# 2020can_master_v5.net
KiCad netlist of a schematic drawn in EAGLE
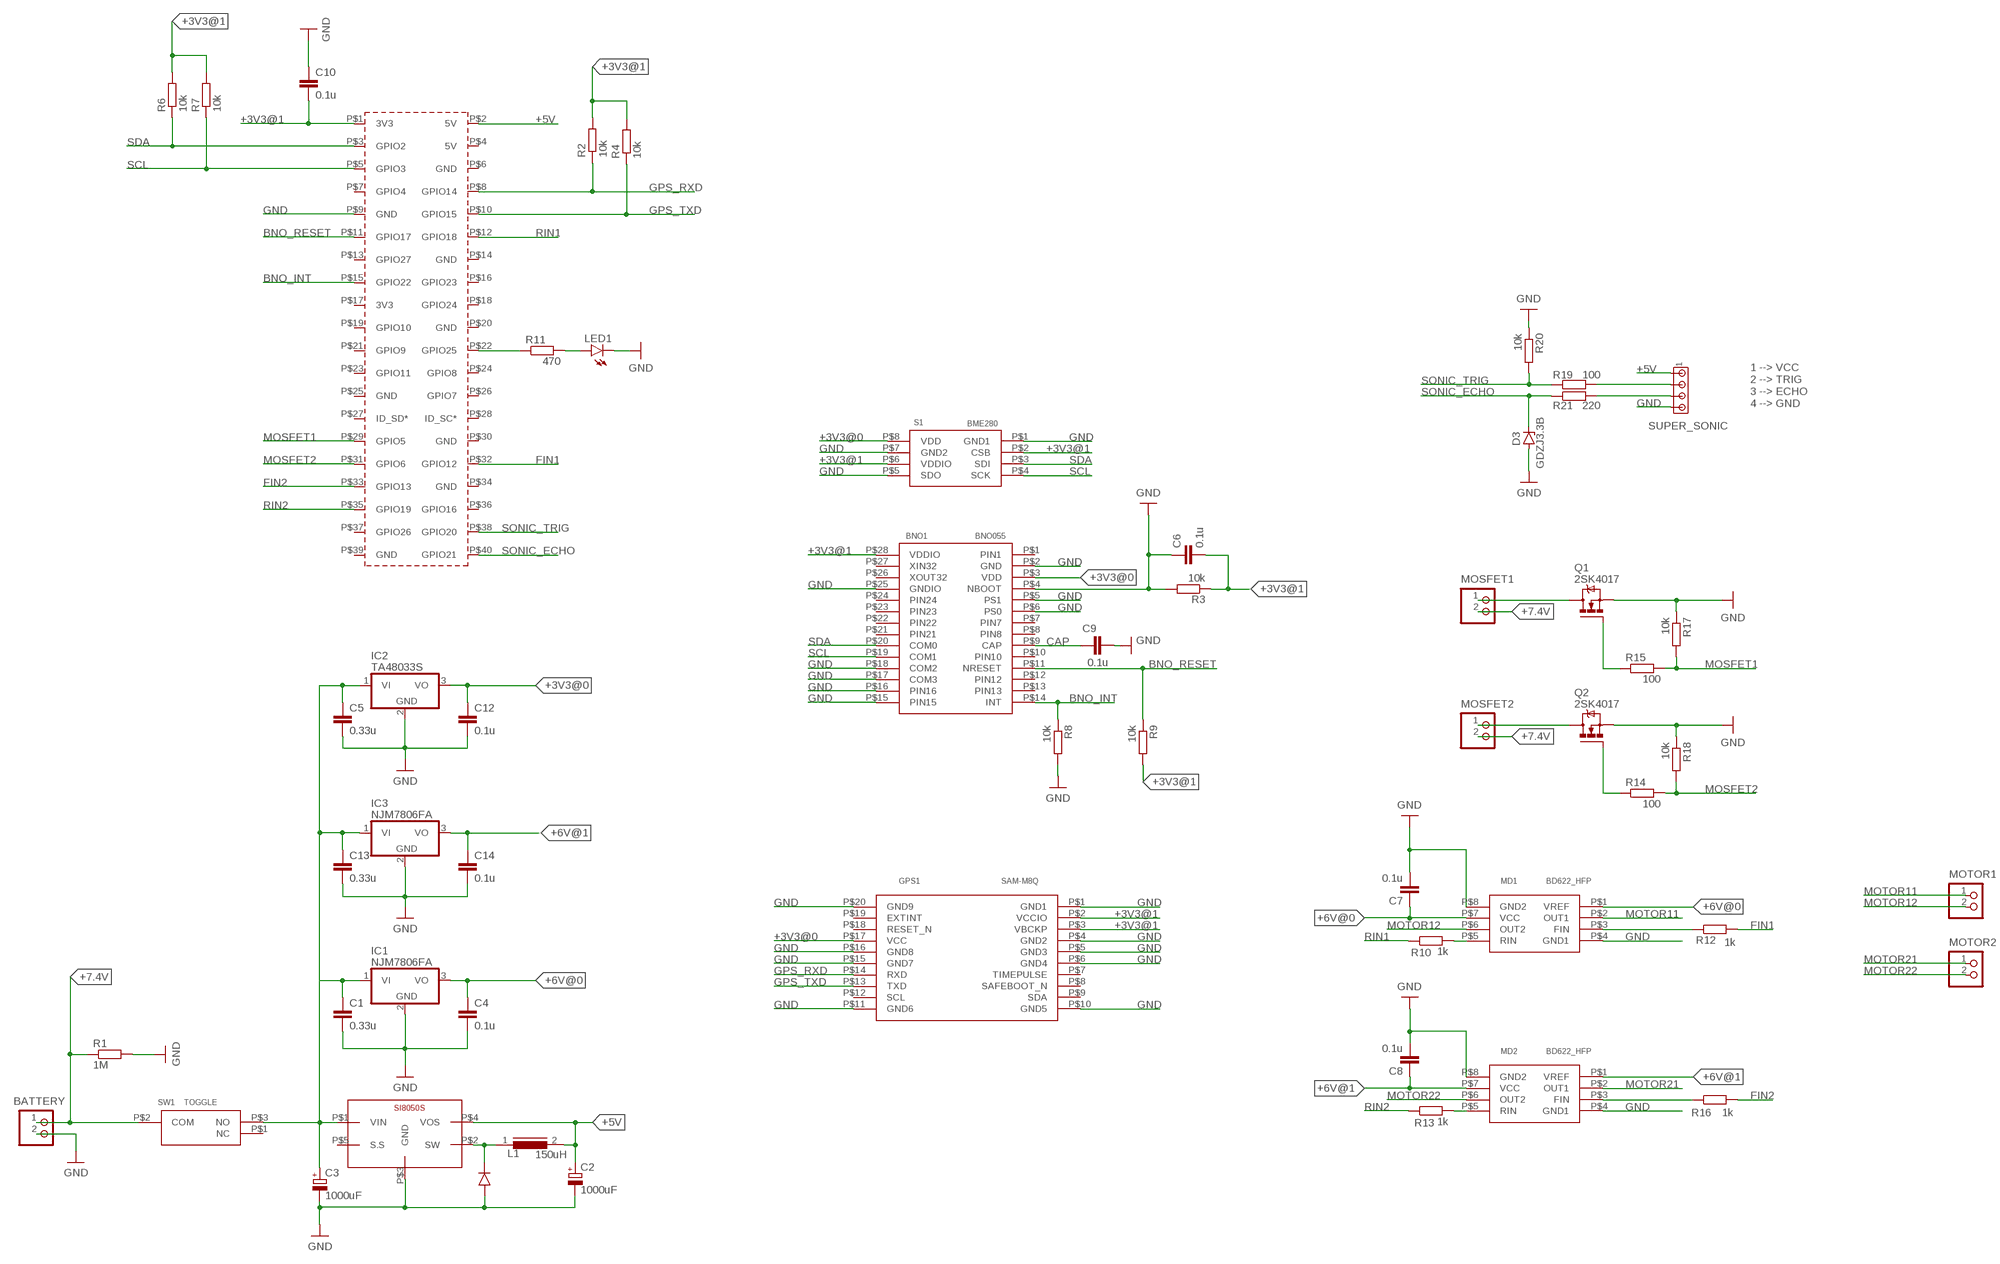
[diagram p0: schematic, sheet 1]

(export (version "E")
  (design (tool "Eeschema 10.0.6"))
  (components
    (comp (ref "BATTERY")
      (value "B2P-VH")
      (footprint "eagle-import:B2P-VH")
      (libsource (lib "eagle-import") (part "B2P-VH"))
    )
    (comp (ref "BNO1")
      (value "BNO055")
      (footprint "eagle-import:BNO055")
      (libsource (lib "eagle-import") (part "BNO055"))
    )
    (comp (ref "C1")
      (value "0.33u")
      (footprint "eagle-import:C5B3")
      (libsource (lib "eagle-import") (part "C5/3"))
    )
    (comp (ref "C2")
      (value "1000uF")
      (footprint "eagle-import:E5-10,5")
      (libsource (lib "eagle-import") (part "CPOL-EUE5-10.5"))
    )
    (comp (ref "C3")
      (value "1000uF")
      (footprint "eagle-import:E5-10,5")
      (libsource (lib "eagle-import") (part "CPOL-EUE5-10.5"))
    )
    (comp (ref "C4")
      (value "0.1u")
      (footprint "eagle-import:C5B3")
      (libsource (lib "eagle-import") (part "C5/3"))
    )
    (comp (ref "C5")
      (value "0.33u")
      (footprint "eagle-import:C5B3")
      (libsource (lib "eagle-import") (part "C5/3"))
    )
    (comp (ref "C6")
      (value "0.1u")
      (footprint "eagle-import:C1206")
      (libsource (lib "eagle-import") (part "C-EUC1206"))
    )
    (comp (ref "C7")
      (value "0.1u")
      (footprint "eagle-import:C1206")
      (libsource (lib "eagle-import") (part "C-EUC1206"))
    )
    (comp (ref "C8")
      (value "0.1u")
      (footprint "eagle-import:C1206")
      (libsource (lib "eagle-import") (part "C-EUC1206"))
    )
    (comp (ref "C9")
      (value "0.1u")
      (footprint "eagle-import:C1206")
      (libsource (lib "eagle-import") (part "C-EUC1206"))
    )
    (comp (ref "C10")
      (value "0.1u")
      (footprint "eagle-import:C1206")
      (libsource (lib "eagle-import") (part "C-EUC1206"))
    )
    (comp (ref "C12")
      (value "0.1u")
      (footprint "eagle-import:C5B3")
      (libsource (lib "eagle-import") (part "C5/3"))
    )
    (comp (ref "C13")
      (value "0.33u")
      (footprint "eagle-import:C5B3")
      (libsource (lib "eagle-import") (part "C5/3"))
    )
    (comp (ref "C14")
      (value "0.1u")
      (footprint "eagle-import:C5B3")
      (libsource (lib "eagle-import") (part "C5/3"))
    )
    (comp (ref "D3")
      (value "GDZJ3.3B")
      (footprint "eagle-import:DO35Z10")
      (libsource (lib "eagle-import") (part "1N821"))
    )
    (comp (ref "DIODE_1.1")
      (value "DIODE_1.5")
      (footprint "eagle-import:DIODE_1.5")
      (libsource (lib "eagle-import") (part "DIODE_1.5"))
    )
    (comp (ref "GPS1")
      (value "SAM-M8Q")
      (footprint "eagle-import:SAM-M8Q")
      (libsource (lib "eagle-import") (part "SAM-M8Q"))
    )
    (comp (ref "IC1")
      (value "NJM7806FA")
      (footprint "eagle-import:TO220V")
      (libsource (lib "eagle-import") (part "78TV6"))
    )
    (comp (ref "IC2")
      (value "TA48033S")
      (footprint "eagle-import:TO220V")
      (libsource (lib "eagle-import") (part "78TV6"))
    )
    (comp (ref "IC3")
      (value "NJM7806FA")
      (footprint "eagle-import:TO220V")
      (libsource (lib "eagle-import") (part "78TV6"))
    )
    (comp (ref "L1")
      (value "150uH")
      (footprint "eagle-import:SFT830D")
      (libsource (lib "eagle-import") (part "SFT830D"))
    )
    (comp (ref "LED1")
      (value "LED5MM")
      (footprint "eagle-import:LED5MM")
      (libsource (lib "eagle-import") (part "LED5MM"))
    )
    (comp (ref "MD1")
      (value "BD622_HFP")
      (footprint "eagle-import:BD62___HRP7")
      (libsource (lib "eagle-import") (part "BD622_HFP"))
    )
    (comp (ref "MD2")
      (value "BD622_HFP")
      (footprint "eagle-import:BD62___HRP7")
      (libsource (lib "eagle-import") (part "BD622_HFP"))
    )
    (comp (ref "MOSFET1")
      (value "B2P-VH")
      (footprint "eagle-import:B2P-VH")
      (libsource (lib "eagle-import") (part "B2P-VH"))
    )
    (comp (ref "MOSFET2")
      (value "B2P-VH")
      (footprint "eagle-import:B2P-VH")
      (libsource (lib "eagle-import") (part "B2P-VH"))
    )
    (comp (ref "MOTOR1")
      (value "B2P-VH")
      (footprint "eagle-import:B2P-VH")
      (libsource (lib "eagle-import") (part "B2P-VH"))
    )
    (comp (ref "MOTOR2")
      (value "B2P-VH")
      (footprint "eagle-import:B2P-VH")
      (libsource (lib "eagle-import") (part "B2P-VH"))
    )
    (comp (ref "PCB1")
      (value "RPI3RPI3")
      (footprint "eagle-import:RPI3")
      (libsource (lib "eagle-import") (part "RPI3RPI3"))
    )
    (comp (ref "Q1")
      (value "2SK4017")
      (footprint "eagle-import:TO220BV")
      (libsource (lib "eagle-import") (part "IRF520"))
    )
    (comp (ref "Q2")
      (value "2SK4017")
      (footprint "eagle-import:TO220BV")
      (libsource (lib "eagle-import") (part "IRF520"))
    )
    (comp (ref "R1")
      (value "1M")
      (footprint "eagle-import:R2012")
      (libsource (lib "eagle-import") (part "R-EU_R2012"))
    )
    (comp (ref "R2")
      (value "10k")
      (footprint "eagle-import:R2012")
      (libsource (lib "eagle-import") (part "R-EU_R2012"))
    )
    (comp (ref "R3")
      (value "10k")
      (footprint "eagle-import:R2012")
      (libsource (lib "eagle-import") (part "R-EU_R2012"))
    )
    (comp (ref "R4")
      (value "10k")
      (footprint "eagle-import:R2012")
      (libsource (lib "eagle-import") (part "R-EU_R2012"))
    )
    (comp (ref "R6")
      (value "10k")
      (footprint "eagle-import:R2012")
      (libsource (lib "eagle-import") (part "R-EU_R2012"))
    )
    (comp (ref "R7")
      (value "10k")
      (footprint "eagle-import:R2012")
      (libsource (lib "eagle-import") (part "R-EU_R2012"))
    )
    (comp (ref "R8")
      (value "10k")
      (footprint "eagle-import:R2012")
      (libsource (lib "eagle-import") (part "R-EU_R2012"))
    )
    (comp (ref "R9")
      (value "10k")
      (footprint "eagle-import:R2012")
      (libsource (lib "eagle-import") (part "R-EU_R2012"))
    )
    (comp (ref "R10")
      (value "1k")
      (footprint "eagle-import:R2012")
      (libsource (lib "eagle-import") (part "R-EU_R2012"))
    )
    (comp (ref "R11")
      (value "470")
      (footprint "eagle-import:0207_10")
      (libsource (lib "eagle-import") (part "R-EU_0207/10"))
    )
    (comp (ref "R12")
      (value "1k")
      (footprint "eagle-import:R2012")
      (libsource (lib "eagle-import") (part "R-EU_R2012"))
    )
    (comp (ref "R13")
      (value "1k")
      (footprint "eagle-import:R2012")
      (libsource (lib "eagle-import") (part "R-EU_R2012"))
    )
    (comp (ref "R14")
      (value "100")
      (footprint "eagle-import:0207_10")
      (libsource (lib "eagle-import") (part "R-EU_0207/10"))
    )
    (comp (ref "R15")
      (value "100")
      (footprint "eagle-import:0207_10")
      (libsource (lib "eagle-import") (part "R-EU_0207/10"))
    )
    (comp (ref "R16")
      (value "1k")
      (footprint "eagle-import:R2012")
      (libsource (lib "eagle-import") (part "R-EU_R2012"))
    )
    (comp (ref "R17")
      (value "10k")
      (footprint "eagle-import:R2012")
      (libsource (lib "eagle-import") (part "R-EU_R2012"))
    )
    (comp (ref "R18")
      (value "10k")
      (footprint "eagle-import:R2012")
      (libsource (lib "eagle-import") (part "R-EU_R2012"))
    )
    (comp (ref "R19")
      (value "100")
      (footprint "eagle-import:0207_10")
      (libsource (lib "eagle-import") (part "R-EU_0207/10"))
    )
    (comp (ref "R20")
      (value "10k")
      (footprint "eagle-import:R2012")
      (libsource (lib "eagle-import") (part "R-EU_R2012"))
    )
    (comp (ref "R21")
      (value "220")
      (footprint "eagle-import:0207_10")
      (libsource (lib "eagle-import") (part "R-EU_0207/10"))
    )
    (comp (ref "S1")
      (value "BME280")
      (footprint "eagle-import:BME280")
      (libsource (lib "eagle-import") (part "BME280"))
    )
    (comp (ref "SI8050S1")
      (value "SI8050S")
      (footprint "eagle-import:SI8050S")
      (libsource (lib "eagle-import") (part "SI8050S"))
    )
    (comp (ref "SUPER_SONIC")
      (value "MTA04-100")
      (footprint "eagle-import:10X04MTA")
      (libsource (lib "eagle-import") (part "MTA04-100"))
    )
    (comp (ref "SW1")
      (value "TOGGLE")
      (footprint "eagle-import:TOGGLE_1MS1-T1-B1-M2-Q-N-S")
      (libsource (lib "eagle-import") (part "TOGGLE_1MS1-T1-B1-M2-Q-N-S"))
    )
  )
  (nets
    (net (code "1") (name "+3V3@0") (class "Default")
      (node (ref "BNO1") (pin "P$3") (pinfunction "VDD_P$3") (pintype "bidirectional"))
      (node (ref "C12") (pin "1") (pinfunction "1_1") (pintype "passive"))
      (node (ref "GPS1") (pin "P$17") (pinfunction "VCC_P$17") (pintype "bidirectional"))
      (node (ref "IC2") (pin "3") (pinfunction "VO_3") (pintype "passive"))
      (node (ref "S1") (pin "P$8") (pinfunction "VDD_P$8") (pintype "bidirectional"))
    )
    (net (code "2") (name "+3V3@1") (class "Default")
      (node (ref "BNO1") (pin "P$28") (pinfunction "VDDIO_P$28") (pintype "bidirectional"))
      (node (ref "C10") (pin "2") (pinfunction "2_2") (pintype "passive"))
      (node (ref "C6") (pin "2") (pinfunction "2_2") (pintype "passive"))
      (node (ref "GPS1") (pin "P$2") (pinfunction "VCCIO_P$2") (pintype "bidirectional"))
      (node (ref "GPS1") (pin "P$3") (pinfunction "VBCKP_P$3") (pintype "bidirectional"))
      (node (ref "PCB1") (pin "P$1") (pinfunction "3V3_P$1") (pintype "bidirectional"))
      (node (ref "R2") (pin "2") (pinfunction "2_2") (pintype "passive"))
      (node (ref "R3") (pin "1") (pinfunction "1_1") (pintype "passive"))
      (node (ref "R4") (pin "2") (pinfunction "2_2") (pintype "passive"))
      (node (ref "R6") (pin "2") (pinfunction "2_2") (pintype "passive"))
      (node (ref "R7") (pin "2") (pinfunction "2_2") (pintype "passive"))
      (node (ref "R9") (pin "2") (pinfunction "2_2") (pintype "passive"))
      (node (ref "S1") (pin "P$2") (pinfunction "CSB_P$2") (pintype "bidirectional"))
      (node (ref "S1") (pin "P$6") (pinfunction "VDDIO_P$6") (pintype "bidirectional"))
    )
    (net (code "3") (name "+5V") (class "Default")
      (node (ref "C2") (pin "+") (pinfunction "+_+") (pintype "passive"))
      (node (ref "L1") (pin "2") (pinfunction "2_2") (pintype "passive"))
      (node (ref "PCB1") (pin "P$2") (pinfunction "5V_P$2") (pintype "bidirectional"))
      (node (ref "SI8050S1") (pin "P$4") (pinfunction "VOS_P$4") (pintype "bidirectional"))
      (node (ref "SUPER_SONIC") (pin "1") (pinfunction "1_1") (pintype "passive"))
    )
    (net (code "4") (name "+6V@0") (class "Default")
      (node (ref "C4") (pin "1") (pinfunction "1_1") (pintype "passive"))
      (node (ref "C7") (pin "1") (pinfunction "1_1") (pintype "passive"))
      (node (ref "IC1") (pin "3") (pinfunction "VO_3") (pintype "passive"))
      (node (ref "MD1") (pin "P$1") (pinfunction "VREF_P$1") (pintype "bidirectional"))
      (node (ref "MD1") (pin "P$7") (pinfunction "VCC_P$7") (pintype "bidirectional"))
    )
    (net (code "5") (name "+6V@1") (class "Default")
      (node (ref "C14") (pin "1") (pinfunction "1_1") (pintype "passive"))
      (node (ref "C8") (pin "1") (pinfunction "1_1") (pintype "passive"))
      (node (ref "IC3") (pin "3") (pinfunction "VO_3") (pintype "passive"))
      (node (ref "MD2") (pin "P$1") (pinfunction "VREF_P$1") (pintype "bidirectional"))
      (node (ref "MD2") (pin "P$7") (pinfunction "VCC_P$7") (pintype "bidirectional"))
    )
    (net (code "6") (name "+7.4V") (class "Default")
      (node (ref "BATTERY") (pin "1") (pinfunction "1_1") (pintype "passive"))
      (node (ref "MOSFET1") (pin "2") (pinfunction "2_2") (pintype "passive"))
      (node (ref "MOSFET2") (pin "2") (pinfunction "2_2") (pintype "passive"))
      (node (ref "R1") (pin "1") (pinfunction "1_1") (pintype "passive"))
      (node (ref "SW1") (pin "P$2") (pinfunction "COM_P$2") (pintype "bidirectional"))
    )
    (net (code "7") (name "/BNO_INT") (class "Default")
      (node (ref "BNO1") (pin "P$14") (pinfunction "INT_P$14") (pintype "bidirectional"))
      (node (ref "PCB1") (pin "P$15") (pinfunction "GPIO22_P$15") (pintype "bidirectional"))
      (node (ref "R8") (pin "1") (pinfunction "1_1") (pintype "passive"))
    )
    (net (code "8") (name "/BNO_RESET") (class "Default")
      (node (ref "BNO1") (pin "P$11") (pinfunction "NRESET_P$11") (pintype "bidirectional"))
      (node (ref "PCB1") (pin "P$11") (pinfunction "GPIO17_P$11") (pintype "bidirectional"))
      (node (ref "R9") (pin "1") (pinfunction "1_1") (pintype "passive"))
    )
    (net (code "9") (name "/CAP") (class "Default")
      (node (ref "BNO1") (pin "P$9") (pinfunction "CAP_P$9") (pintype "bidirectional"))
      (node (ref "C9") (pin "1") (pinfunction "1_1") (pintype "passive"))
    )
    (net (code "10") (name "/FIN1") (class "Default")
      (node (ref "PCB1") (pin "P$32") (pinfunction "GPIO12_P$32") (pintype "bidirectional"))
      (node (ref "R12") (pin "2") (pinfunction "2_2") (pintype "passive"))
    )
    (net (code "11") (name "/FIN2") (class "Default")
      (node (ref "PCB1") (pin "P$33") (pinfunction "GPIO13_P$33") (pintype "bidirectional"))
      (node (ref "R16") (pin "2") (pinfunction "2_2") (pintype "passive"))
    )
    (net (code "12") (name "/GPS_RXD") (class "Default")
      (node (ref "GPS1") (pin "P$14") (pinfunction "RXD_P$14") (pintype "bidirectional"))
      (node (ref "PCB1") (pin "P$8") (pinfunction "GPIO14_P$8") (pintype "bidirectional"))
      (node (ref "R2") (pin "1") (pinfunction "1_1") (pintype "passive"))
    )
    (net (code "13") (name "/GPS_TXD") (class "Default")
      (node (ref "GPS1") (pin "P$13") (pinfunction "TXD_P$13") (pintype "bidirectional"))
      (node (ref "PCB1") (pin "P$10") (pinfunction "GPIO15_P$10") (pintype "bidirectional"))
      (node (ref "R4") (pin "1") (pinfunction "1_1") (pintype "passive"))
    )
    (net (code "14") (name "/MOSFET1") (class "Default")
      (node (ref "PCB1") (pin "P$29") (pinfunction "GPIO5_P$29") (pintype "bidirectional"))
      (node (ref "R15") (pin "2") (pinfunction "2_2") (pintype "passive"))
      (node (ref "R17") (pin "2") (pinfunction "2_2") (pintype "passive"))
    )
    (net (code "15") (name "/MOSFET2") (class "Default")
      (node (ref "PCB1") (pin "P$31") (pinfunction "GPIO6_P$31") (pintype "bidirectional"))
      (node (ref "R14") (pin "2") (pinfunction "2_2") (pintype "passive"))
      (node (ref "R18") (pin "2") (pinfunction "2_2") (pintype "passive"))
    )
    (net (code "16") (name "/MOTOR11") (class "Default")
      (node (ref "MD1") (pin "P$2") (pinfunction "OUT1_P$2") (pintype "bidirectional"))
      (node (ref "MOTOR1") (pin "1") (pinfunction "1_1") (pintype "passive"))
    )
    (net (code "17") (name "/MOTOR12") (class "Default")
      (node (ref "MD1") (pin "P$6") (pinfunction "OUT2_P$6") (pintype "bidirectional"))
      (node (ref "MOTOR1") (pin "2") (pinfunction "2_2") (pintype "passive"))
    )
    (net (code "18") (name "/MOTOR21") (class "Default")
      (node (ref "MD2") (pin "P$2") (pinfunction "OUT1_P$2") (pintype "bidirectional"))
      (node (ref "MOTOR2") (pin "1") (pinfunction "1_1") (pintype "passive"))
    )
    (net (code "19") (name "/MOTOR22") (class "Default")
      (node (ref "MD2") (pin "P$6") (pinfunction "OUT2_P$6") (pintype "bidirectional"))
      (node (ref "MOTOR2") (pin "2") (pinfunction "2_2") (pintype "passive"))
    )
    (net (code "20") (name "/RIN1") (class "Default")
      (node (ref "PCB1") (pin "P$12") (pinfunction "GPIO18_P$12") (pintype "bidirectional"))
      (node (ref "R10") (pin "1") (pinfunction "1_1") (pintype "passive"))
    )
    (net (code "21") (name "/RIN2") (class "Default")
      (node (ref "PCB1") (pin "P$35") (pinfunction "GPIO19_P$35") (pintype "bidirectional"))
      (node (ref "R13") (pin "1") (pinfunction "1_1") (pintype "passive"))
    )
    (net (code "22") (name "/SCL") (class "Default")
      (node (ref "BNO1") (pin "P$19") (pinfunction "COM1_P$19") (pintype "bidirectional"))
      (node (ref "PCB1") (pin "P$5") (pinfunction "GPIO3_P$5") (pintype "bidirectional"))
      (node (ref "R7") (pin "1") (pinfunction "1_1") (pintype "passive"))
      (node (ref "S1") (pin "P$4") (pinfunction "SCK_P$4") (pintype "bidirectional"))
    )
    (net (code "23") (name "/SDA") (class "Default")
      (node (ref "BNO1") (pin "P$20") (pinfunction "COM0_P$20") (pintype "bidirectional"))
      (node (ref "PCB1") (pin "P$3") (pinfunction "GPIO2_P$3") (pintype "bidirectional"))
      (node (ref "R6") (pin "1") (pinfunction "1_1") (pintype "passive"))
      (node (ref "S1") (pin "P$3") (pinfunction "SDI_P$3") (pintype "bidirectional"))
    )
    (net (code "24") (name "/SONIC_ECHO") (class "Default")
      (node (ref "D3") (pin "C") (pinfunction "C_C") (pintype "passive"))
      (node (ref "PCB1") (pin "P$40") (pinfunction "GPIO21_P$40") (pintype "bidirectional"))
      (node (ref "R21") (pin "1") (pinfunction "1_1") (pintype "passive"))
    )
    (net (code "25") (name "/SONIC_TRIG") (class "Default")
      (node (ref "PCB1") (pin "P$38") (pinfunction "GPIO20_P$38") (pintype "bidirectional"))
      (node (ref "R19") (pin "1") (pinfunction "1_1") (pintype "passive"))
      (node (ref "R20") (pin "2") (pinfunction "2_2") (pintype "passive"))
    )
    (net (code "26") (name "GND") (class "Default")
      (node (ref "BATTERY") (pin "2") (pinfunction "2_2") (pintype "passive"))
      (node (ref "BNO1") (pin "P$15") (pinfunction "PIN15_P$15") (pintype "bidirectional"))
      (node (ref "BNO1") (pin "P$16") (pinfunction "PIN16_P$16") (pintype "bidirectional"))
      (node (ref "BNO1") (pin "P$17") (pinfunction "COM3_P$17") (pintype "bidirectional"))
      (node (ref "BNO1") (pin "P$18") (pinfunction "COM2_P$18") (pintype "bidirectional"))
      (node (ref "BNO1") (pin "P$2") (pinfunction "GND_P$2") (pintype "bidirectional"))
      (node (ref "BNO1") (pin "P$25") (pinfunction "GNDIO_P$25") (pintype "bidirectional"))
      (node (ref "BNO1") (pin "P$4") (pinfunction "NBOOT_P$4") (pintype "bidirectional"))
      (node (ref "BNO1") (pin "P$5") (pinfunction "PS1_P$5") (pintype "bidirectional"))
      (node (ref "BNO1") (pin "P$6") (pinfunction "PS0_P$6") (pintype "bidirectional"))
      (node (ref "C1") (pin "2") (pinfunction "2_2") (pintype "passive"))
      (node (ref "C10") (pin "1") (pinfunction "1_1") (pintype "passive"))
      (node (ref "C12") (pin "2") (pinfunction "2_2") (pintype "passive"))
      (node (ref "C2") (pin "-") (pinfunction "-_-") (pintype "passive"))
      (node (ref "C3") (pin "-") (pinfunction "-_-") (pintype "passive"))
      (node (ref "C4") (pin "2") (pinfunction "2_2") (pintype "passive"))
      (node (ref "C5") (pin "2") (pinfunction "2_2") (pintype "passive"))
      (node (ref "C6") (pin "1") (pinfunction "1_1") (pintype "passive"))
      (node (ref "C7") (pin "2") (pinfunction "2_2") (pintype "passive"))
      (node (ref "C8") (pin "2") (pinfunction "2_2") (pintype "passive"))
      (node (ref "C9") (pin "2") (pinfunction "2_2") (pintype "passive"))
      (node (ref "D3") (pin "A") (pinfunction "A_A") (pintype "passive"))
      (node (ref "DIODE_1.1") (pin "P$1") (pinfunction "ANODE_P$1") (pintype "bidirectional"))
      (node (ref "GPS1") (pin "P$1") (pinfunction "GND1_P$1") (pintype "bidirectional"))
      (node (ref "GPS1") (pin "P$10") (pinfunction "GND5_P$10") (pintype "bidirectional"))
      (node (ref "GPS1") (pin "P$11") (pinfunction "GND6_P$11") (pintype "bidirectional"))
      (node (ref "GPS1") (pin "P$15") (pinfunction "GND7_P$15") (pintype "bidirectional"))
      (node (ref "GPS1") (pin "P$16") (pinfunction "GND8_P$16") (pintype "bidirectional"))
      (node (ref "GPS1") (pin "P$20") (pinfunction "GND9_P$20") (pintype "bidirectional"))
      (node (ref "GPS1") (pin "P$4") (pinfunction "GND2_P$4") (pintype "bidirectional"))
      (node (ref "GPS1") (pin "P$5") (pinfunction "GND3_P$5") (pintype "bidirectional"))
      (node (ref "GPS1") (pin "P$6") (pinfunction "GND4_P$6") (pintype "bidirectional"))
      (node (ref "IC1") (pin "2") (pinfunction "GND_2") (pintype "passive"))
      (node (ref "IC2") (pin "2") (pinfunction "GND_2") (pintype "passive"))
      (node (ref "LED1") (pin "K") (pinfunction "C_K") (pintype "passive"))
      (node (ref "MD1") (pin "P$4") (pinfunction "GND1_P$4") (pintype "bidirectional"))
      (node (ref "MD1") (pin "P$8") (pinfunction "GND2_P$8") (pintype "bidirectional"))
      (node (ref "MD2") (pin "P$4") (pinfunction "GND1_P$4") (pintype "bidirectional"))
      (node (ref "MD2") (pin "P$8") (pinfunction "GND2_P$8") (pintype "bidirectional"))
      (node (ref "PCB1") (pin "P$9") (pinfunction "GND_P$9") (pintype "bidirectional"))
      (node (ref "Q1") (pin "S") (pinfunction "S_S") (pintype "passive"))
      (node (ref "Q2") (pin "S") (pinfunction "S_S") (pintype "passive"))
      (node (ref "R1") (pin "2") (pinfunction "2_2") (pintype "passive"))
      (node (ref "R17") (pin "1") (pinfunction "1_1") (pintype "passive"))
      (node (ref "R18") (pin "1") (pinfunction "1_1") (pintype "passive"))
      (node (ref "R20") (pin "1") (pinfunction "1_1") (pintype "passive"))
      (node (ref "R3") (pin "2") (pinfunction "2_2") (pintype "passive"))
      (node (ref "R8") (pin "2") (pinfunction "2_2") (pintype "passive"))
      (node (ref "S1") (pin "P$1") (pinfunction "GND1_P$1") (pintype "bidirectional"))
      (node (ref "S1") (pin "P$5") (pinfunction "SDO_P$5") (pintype "bidirectional"))
      (node (ref "S1") (pin "P$7") (pinfunction "GND2_P$7") (pintype "bidirectional"))
      (node (ref "SI8050S1") (pin "P$3") (pinfunction "GND_P$3") (pintype "bidirectional"))
      (node (ref "SUPER_SONIC") (pin "4") (pinfunction "4_4") (pintype "passive"))
    )
    (net (code "27") (name "Net-(DIODE_1.1-CATHODE)") (class "Default")
      (node (ref "DIODE_1.1") (pin "P$2") (pinfunction "CATHODE_P$2") (pintype "bidirectional"))
      (node (ref "L1") (pin "1") (pinfunction "1_1") (pintype "passive"))
      (node (ref "SI8050S1") (pin "P$2") (pinfunction "SW_P$2") (pintype "bidirectional"))
    )
    (net (code "28") (name "Net-(IC1-VI)") (class "Default")
      (node (ref "C1") (pin "1") (pinfunction "1_1") (pintype "passive"))
      (node (ref "C13") (pin "1") (pinfunction "1_1") (pintype "passive"))
      (node (ref "C3") (pin "+") (pinfunction "+_+") (pintype "passive"))
      (node (ref "C5") (pin "1") (pinfunction "1_1") (pintype "passive"))
      (node (ref "IC1") (pin "1") (pinfunction "VI_1") (pintype "input"))
      (node (ref "IC2") (pin "1") (pinfunction "VI_1") (pintype "input"))
      (node (ref "IC3") (pin "1") (pinfunction "VI_1") (pintype "input"))
      (node (ref "SI8050S1") (pin "P$1") (pinfunction "VIN_P$1") (pintype "bidirectional"))
      (node (ref "SW1") (pin "P$3") (pinfunction "NO_P$3") (pintype "bidirectional"))
    )
    (net (code "29") (name "Net-(IC3-GND)") (class "Default")
      (node (ref "C13") (pin "2") (pinfunction "2_2") (pintype "passive"))
      (node (ref "C14") (pin "2") (pinfunction "2_2") (pintype "passive"))
      (node (ref "IC3") (pin "2") (pinfunction "GND_2") (pintype "passive"))
    )
    (net (code "30") (name "Net-(LED1-PadA)") (class "Default")
      (node (ref "LED1") (pin "A") (pinfunction "A_A") (pintype "passive"))
      (node (ref "R11") (pin "2") (pinfunction "2_2") (pintype "passive"))
    )
    (net (code "31") (name "Net-(MD1-FIN)") (class "Default")
      (node (ref "MD1") (pin "P$3") (pinfunction "FIN_P$3") (pintype "bidirectional"))
      (node (ref "R12") (pin "1") (pinfunction "1_1") (pintype "passive"))
    )
    (net (code "32") (name "Net-(MD1-RIN)") (class "Default")
      (node (ref "MD1") (pin "P$5") (pinfunction "RIN_P$5") (pintype "bidirectional"))
      (node (ref "R10") (pin "2") (pinfunction "2_2") (pintype "passive"))
    )
    (net (code "33") (name "Net-(MD2-FIN)") (class "Default")
      (node (ref "MD2") (pin "P$3") (pinfunction "FIN_P$3") (pintype "bidirectional"))
      (node (ref "R16") (pin "1") (pinfunction "1_1") (pintype "passive"))
    )
    (net (code "34") (name "Net-(MD2-RIN)") (class "Default")
      (node (ref "MD2") (pin "P$5") (pinfunction "RIN_P$5") (pintype "bidirectional"))
      (node (ref "R13") (pin "2") (pinfunction "2_2") (pintype "passive"))
    )
    (net (code "35") (name "Net-(MOSFET1-Pad1)") (class "Default")
      (node (ref "MOSFET1") (pin "1") (pinfunction "1_1") (pintype "passive"))
      (node (ref "Q1") (pin "D") (pinfunction "D_D") (pintype "passive"))
    )
    (net (code "36") (name "Net-(MOSFET2-Pad1)") (class "Default")
      (node (ref "MOSFET2") (pin "1") (pinfunction "1_1") (pintype "passive"))
      (node (ref "Q2") (pin "D") (pinfunction "D_D") (pintype "passive"))
    )
    (net (code "37") (name "Net-(PCB1-GPIO25)") (class "Default")
      (node (ref "PCB1") (pin "P$22") (pinfunction "GPIO25_P$22") (pintype "bidirectional"))
      (node (ref "R11") (pin "1") (pinfunction "1_1") (pintype "passive"))
    )
    (net (code "38") (name "Net-(Q1-PadG)") (class "Default")
      (node (ref "Q1") (pin "G") (pinfunction "G_G") (pintype "passive"))
      (node (ref "R15") (pin "1") (pinfunction "1_1") (pintype "passive"))
    )
    (net (code "39") (name "Net-(Q2-PadG)") (class "Default")
      (node (ref "Q2") (pin "G") (pinfunction "G_G") (pintype "passive"))
      (node (ref "R14") (pin "1") (pinfunction "1_1") (pintype "passive"))
    )
    (net (code "40") (name "Net-(R19-Pad2)") (class "Default")
      (node (ref "R19") (pin "2") (pinfunction "2_2") (pintype "passive"))
      (node (ref "SUPER_SONIC") (pin "2") (pinfunction "2_2") (pintype "passive"))
    )
    (net (code "41") (name "Net-(R21-Pad2)") (class "Default")
      (node (ref "R21") (pin "2") (pinfunction "2_2") (pintype "passive"))
      (node (ref "SUPER_SONIC") (pin "3") (pinfunction "3_3") (pintype "passive"))
    )
    (net (code "42") (name "unconnected-(BNO1-PIN1-PadP$1)") (class "Default")
      (node (ref "BNO1") (pin "P$1") (pinfunction "PIN1_P$1") (pintype "bidirectional"))
    )
    (net (code "43") (name "unconnected-(BNO1-PIN7-PadP$7)") (class "Default")
      (node (ref "BNO1") (pin "P$7") (pinfunction "PIN7_P$7") (pintype "bidirectional"))
    )
    (net (code "44") (name "unconnected-(BNO1-PIN8-PadP$8)") (class "Default")
      (node (ref "BNO1") (pin "P$8") (pinfunction "PIN8_P$8") (pintype "bidirectional"))
    )
    (net (code "45") (name "unconnected-(BNO1-PIN10-PadP$10)") (class "Default")
      (node (ref "BNO1") (pin "P$10") (pinfunction "PIN10_P$10") (pintype "bidirectional"))
    )
    (net (code "46") (name "unconnected-(BNO1-PIN12-PadP$12)") (class "Default")
      (node (ref "BNO1") (pin "P$12") (pinfunction "PIN12_P$12") (pintype "bidirectional"))
    )
    (net (code "47") (name "unconnected-(BNO1-PIN13-PadP$13)") (class "Default")
      (node (ref "BNO1") (pin "P$13") (pinfunction "PIN13_P$13") (pintype "bidirectional"))
    )
    (net (code "48") (name "unconnected-(BNO1-PIN21-PadP$21)") (class "Default")
      (node (ref "BNO1") (pin "P$21") (pinfunction "PIN21_P$21") (pintype "bidirectional"))
    )
    (net (code "49") (name "unconnected-(BNO1-PIN22-PadP$22)") (class "Default")
      (node (ref "BNO1") (pin "P$22") (pinfunction "PIN22_P$22") (pintype "bidirectional"))
    )
    (net (code "50") (name "unconnected-(BNO1-PIN23-PadP$23)") (class "Default")
      (node (ref "BNO1") (pin "P$23") (pinfunction "PIN23_P$23") (pintype "bidirectional"))
    )
    (net (code "51") (name "unconnected-(BNO1-PIN24-PadP$24)") (class "Default")
      (node (ref "BNO1") (pin "P$24") (pinfunction "PIN24_P$24") (pintype "bidirectional"))
    )
    (net (code "52") (name "unconnected-(BNO1-XIN32-PadP$27)") (class "Default")
      (node (ref "BNO1") (pin "P$27") (pinfunction "XIN32_P$27") (pintype "bidirectional"))
    )
    (net (code "53") (name "unconnected-(BNO1-XOUT32-PadP$26)") (class "Default")
      (node (ref "BNO1") (pin "P$26") (pinfunction "XOUT32_P$26") (pintype "bidirectional"))
    )
    (net (code "54") (name "unconnected-(GPS1-EXTINT-PadP$19)") (class "Default")
      (node (ref "GPS1") (pin "P$19") (pinfunction "EXTINT_P$19") (pintype "bidirectional"))
    )
    (net (code "55") (name "unconnected-(GPS1-RESET_N-PadP$18)") (class "Default")
      (node (ref "GPS1") (pin "P$18") (pinfunction "RESET_N_P$18") (pintype "bidirectional"))
    )
    (net (code "56") (name "unconnected-(GPS1-SAFEBOOT_N-PadP$8)") (class "Default")
      (node (ref "GPS1") (pin "P$8") (pinfunction "SAFEBOOT_N_P$8") (pintype "bidirectional"))
    )
    (net (code "57") (name "unconnected-(GPS1-SCL-PadP$12)") (class "Default")
      (node (ref "GPS1") (pin "P$12") (pinfunction "SCL_P$12") (pintype "bidirectional"))
    )
    (net (code "58") (name "unconnected-(GPS1-SDA-PadP$9)") (class "Default")
      (node (ref "GPS1") (pin "P$9") (pinfunction "SDA_P$9") (pintype "bidirectional"))
    )
    (net (code "59") (name "unconnected-(GPS1-TIMEPULSE-PadP$7)") (class "Default")
      (node (ref "GPS1") (pin "P$7") (pinfunction "TIMEPULSE_P$7") (pintype "bidirectional"))
    )
    (net (code "60") (name "unconnected-(PCB1-3V3-PadP$17)") (class "Default")
      (node (ref "PCB1") (pin "P$17") (pinfunction "3V3_P$17") (pintype "bidirectional"))
    )
    (net (code "61") (name "unconnected-(PCB1-5V-PadP$4)") (class "Default")
      (node (ref "PCB1") (pin "P$4") (pinfunction "5V_P$4") (pintype "bidirectional"))
    )
    (net (code "62") (name "unconnected-(PCB1-GND-PadP$6)") (class "Default")
      (node (ref "PCB1") (pin "P$6") (pinfunction "GND_P$6") (pintype "bidirectional"))
    )
    (net (code "63") (name "unconnected-(PCB1-GND-PadP$14)") (class "Default")
      (node (ref "PCB1") (pin "P$14") (pinfunction "GND_P$14") (pintype "bidirectional"))
    )
    (net (code "64") (name "unconnected-(PCB1-GND-PadP$20)") (class "Default")
      (node (ref "PCB1") (pin "P$20") (pinfunction "GND_P$20") (pintype "bidirectional"))
    )
    (net (code "65") (name "unconnected-(PCB1-GND-PadP$25)") (class "Default")
      (node (ref "PCB1") (pin "P$25") (pinfunction "GND_P$25") (pintype "bidirectional"))
    )
    (net (code "66") (name "unconnected-(PCB1-GND-PadP$30)") (class "Default")
      (node (ref "PCB1") (pin "P$30") (pinfunction "GND_P$30") (pintype "bidirectional"))
    )
    (net (code "67") (name "unconnected-(PCB1-GND-PadP$34)") (class "Default")
      (node (ref "PCB1") (pin "P$34") (pinfunction "GND_P$34") (pintype "bidirectional"))
    )
    (net (code "68") (name "unconnected-(PCB1-GND-PadP$39)") (class "Default")
      (node (ref "PCB1") (pin "P$39") (pinfunction "GND_P$39") (pintype "bidirectional"))
    )
    (net (code "69") (name "unconnected-(PCB1-GPIO4-PadP$7)") (class "Default")
      (node (ref "PCB1") (pin "P$7") (pinfunction "GPIO4_P$7") (pintype "bidirectional"))
    )
    (net (code "70") (name "unconnected-(PCB1-GPIO7-PadP$26)") (class "Default")
      (node (ref "PCB1") (pin "P$26") (pinfunction "GPIO7_P$26") (pintype "bidirectional"))
    )
    (net (code "71") (name "unconnected-(PCB1-GPIO8-PadP$24)") (class "Default")
      (node (ref "PCB1") (pin "P$24") (pinfunction "GPIO8_P$24") (pintype "bidirectional"))
    )
    (net (code "72") (name "unconnected-(PCB1-GPIO9-PadP$21)") (class "Default")
      (node (ref "PCB1") (pin "P$21") (pinfunction "GPIO9_P$21") (pintype "bidirectional"))
    )
    (net (code "73") (name "unconnected-(PCB1-GPIO10-PadP$19)") (class "Default")
      (node (ref "PCB1") (pin "P$19") (pinfunction "GPIO10_P$19") (pintype "bidirectional"))
    )
    (net (code "74") (name "unconnected-(PCB1-GPIO11-PadP$23)") (class "Default")
      (node (ref "PCB1") (pin "P$23") (pinfunction "GPIO11_P$23") (pintype "bidirectional"))
    )
    (net (code "75") (name "unconnected-(PCB1-GPIO16-PadP$36)") (class "Default")
      (node (ref "PCB1") (pin "P$36") (pinfunction "GPIO16_P$36") (pintype "bidirectional"))
    )
    (net (code "76") (name "unconnected-(PCB1-GPIO23-PadP$16)") (class "Default")
      (node (ref "PCB1") (pin "P$16") (pinfunction "GPIO23_P$16") (pintype "bidirectional"))
    )
    (net (code "77") (name "unconnected-(PCB1-GPIO24-PadP$18)") (class "Default")
      (node (ref "PCB1") (pin "P$18") (pinfunction "GPIO24_P$18") (pintype "bidirectional"))
    )
    (net (code "78") (name "unconnected-(PCB1-GPIO26-PadP$37)") (class "Default")
      (node (ref "PCB1") (pin "P$37") (pinfunction "GPIO26_P$37") (pintype "bidirectional"))
    )
    (net (code "79") (name "unconnected-(PCB1-GPIO27-PadP$13)") (class "Default")
      (node (ref "PCB1") (pin "P$13") (pinfunction "GPIO27_P$13") (pintype "bidirectional"))
    )
    (net (code "80") (name "unconnected-(PCB1-ID_SC*-PadP$28)") (class "Default")
      (node (ref "PCB1") (pin "P$28") (pinfunction "ID_SC*_P$28") (pintype "bidirectional"))
    )
    (net (code "81") (name "unconnected-(PCB1-ID_SD*-PadP$27)") (class "Default")
      (node (ref "PCB1") (pin "P$27") (pinfunction "ID_SD*_P$27") (pintype "bidirectional"))
    )
    (net (code "82") (name "unconnected-(SI8050S1-S.S-PadP$5)") (class "Default")
      (node (ref "SI8050S1") (pin "P$5") (pinfunction "S.S_P$5") (pintype "bidirectional"))
    )
    (net (code "83") (name "unconnected-(SW1-NC-PadP$1)") (class "Default")
      (node (ref "SW1") (pin "P$1") (pinfunction "NC_P$1") (pintype "bidirectional"))
    )
  )
)
